# Sheet1.net
KiCad netlist of a schematic drawn in Altium Designer
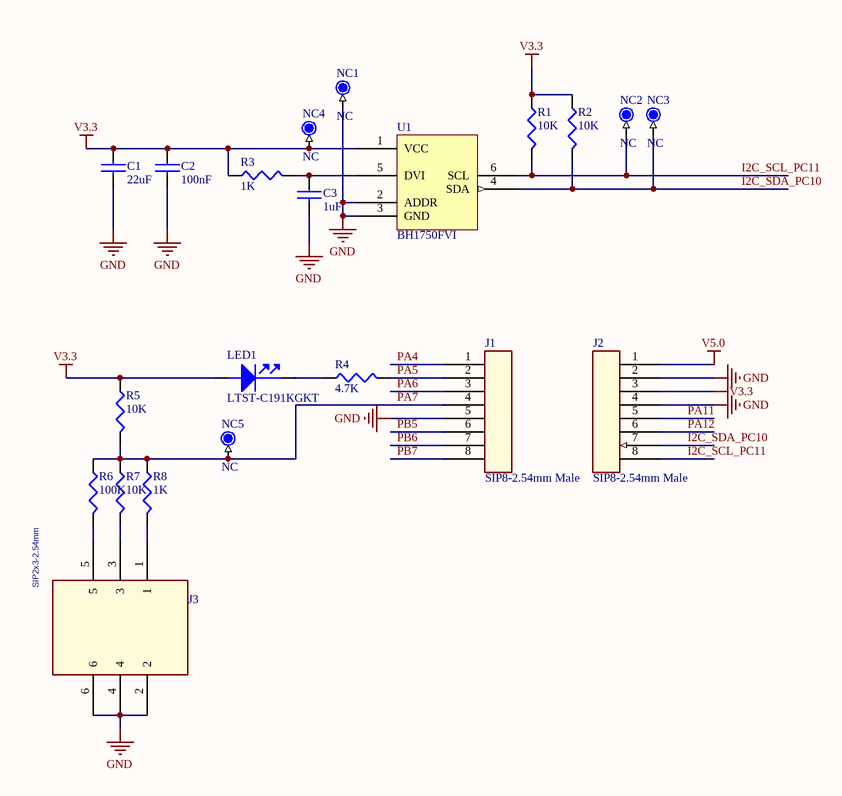
[diagram p0: Sheet1.SchDoc]

(export (version "E")
  (design (tool "Eeschema 10.0.6"))
  (components
    (comp (ref "C1") (value "22uF") (footprint "SC0805") (libsource (lib "EN-C200-OPT") (part "CAP NP")))
    (comp (ref "C2") (value "100nF") (footprint "SC0603") (libsource (lib "EN-C200-OPT") (part "CAP NP")))
    (comp (ref "C3") (value "1uF") (footprint "SC0603") (libsource (lib "EN-C200-OPT") (part "CAP NP")))
    (comp (ref "J1")
      (value "SIP8-2.54mm Male")
      (footprint "SIP-8P-100")
      (libsource (lib "EN-C200-OPT") (part "HEADER8"))
    )
    (comp (ref "J2")
      (value "SIP8-2.54mm Male")
      (footprint "SIP-8P-100")
      (libsource (lib "") (part "HEADER8_1"))
    )
    (comp (ref "J3")
      (value "SIP2x3-2.54mm")
      (footprint "SIP-2X3P-100")
      (libsource (lib "EN-C200-OPT") (part "CON2X3"))
    )
    (comp (ref "LED1")
      (value "LTST-C191KGKT")
      (footprint "HSD0603-LED")
      (libsource (lib "EN-C200-OPT") (part "LED"))
    )
    (comp (ref "NC1") (value "NC") (footprint "TP32-SMD") (libsource (lib "EN-C200-OPT") (part "TP")))
    (comp (ref "NC2") (value "NC") (footprint "TP32-SMD") (libsource (lib "EN-C200-OPT") (part "TP")))
    (comp (ref "NC3") (value "NC") (footprint "TP32-SMD") (libsource (lib "EN-C200-OPT") (part "TP")))
    (comp (ref "NC4") (value "NC") (footprint "TP32-SMD") (libsource (lib "EN-C200-OPT") (part "TP")))
    (comp (ref "NC5") (value "NC") (footprint "TP32-SMD") (libsource (lib "EN-C200-OPT") (part "TP")))
    (comp (ref "R1") (value "10K") (footprint "SR0603") (libsource (lib "EN-C200-OPT") (part "RESISTOR")))
    (comp (ref "R2") (value "10K") (footprint "SR0603") (libsource (lib "EN-C200-OPT") (part "RESISTOR")))
    (comp (ref "R3") (value "1K") (footprint "SR0603") (libsource (lib "EN-C200-OPT") (part "RESISTOR")))
    (comp (ref "R4") (value "4.7K") (footprint "SR0603") (libsource (lib "EN-C200-OPT") (part "RESISTOR")))
    (comp (ref "R5") (value "10K") (footprint "SR0603") (libsource (lib "EN-C200-OPT") (part "RESISTOR")))
    (comp (ref "R6") (value "100K") (footprint "SR0603") (libsource (lib "EN-C200-OPT") (part "RESISTOR")))
    (comp (ref "R7") (value "10K") (footprint "SR0603") (libsource (lib "EN-C200-OPT") (part "RESISTOR")))
    (comp (ref "R8") (value "1K") (footprint "SR0603") (libsource (lib "EN-C200-OPT") (part "RESISTOR")))
    (comp (ref "U1")
      (value "BH1750FVI")
      (footprint "sop6-20-105")
      (description "16 位数字输出型环境光强度传感器 ， I2C  BUS/-40 ℃ ～ +85 ℃")
      (libsource (lib "Schlib1") (part "BH1750FVI"))
    )
  )
  (nets
    (net (code "1") (name "/I2C_SCL_PC11") (class "Default")
      (node (ref "J2") (pin "8") (pinfunction "8_8") (pintype "passive"))
      (node (ref "NC2") (pin "1") (pinfunction "1_1") (pintype "input"))
      (node (ref "R1") (pin "2") (pinfunction "2_2") (pintype "passive"))
      (node (ref "U1") (pin "6") (pinfunction "SCL_6") (pintype "passive"))
    )
    (net (code "2") (name "/I2C_SDA_PC10") (class "Default")
      (node (ref "J2") (pin "7") (pinfunction "7_7") (pintype "input"))
      (node (ref "NC3") (pin "1") (pinfunction "1_1") (pintype "input"))
      (node (ref "R2") (pin "2") (pinfunction "2_2") (pintype "passive"))
      (node (ref "U1") (pin "4") (pinfunction "SDA_4") (pintype "output"))
    )
    (net (code "3") (name "/PA4") (class "Default")
      (node (ref "J1") (pin "1") (pinfunction "1_1") (pintype "passive"))
    )
    (net (code "4") (name "/PA5") (class "Default")
      (node (ref "J1") (pin "2") (pinfunction "2_2") (pintype "passive"))
      (node (ref "R4") (pin "2") (pinfunction "2_2") (pintype "passive"))
    )
    (net (code "5") (name "/PA6") (class "Default")
      (node (ref "J1") (pin "3") (pinfunction "3_3") (pintype "passive"))
    )
    (net (code "6") (name "/PA7") (class "Default")
      (node (ref "J1") (pin "4") (pinfunction "4_4") (pintype "passive"))
      (node (ref "NC5") (pin "1") (pinfunction "1_1") (pintype "input"))
      (node (ref "R5") (pin "2") (pinfunction "2_2") (pintype "passive"))
      (node (ref "R6") (pin "1") (pinfunction "1_1") (pintype "passive"))
      (node (ref "R7") (pin "1") (pinfunction "1_1") (pintype "passive"))
      (node (ref "R8") (pin "1") (pinfunction "1_1") (pintype "passive"))
    )
    (net (code "7") (name "/PA11") (class "Default")
      (node (ref "J2") (pin "5") (pinfunction "5_5") (pintype "passive"))
    )
    (net (code "8") (name "/PA12") (class "Default")
      (node (ref "J2") (pin "6") (pinfunction "6_6") (pintype "passive"))
    )
    (net (code "9") (name "/PB5") (class "Default")
      (node (ref "J1") (pin "6") (pinfunction "6_6") (pintype "passive"))
    )
    (net (code "10") (name "/PB6") (class "Default")
      (node (ref "J1") (pin "7") (pinfunction "7_7") (pintype "passive"))
    )
    (net (code "11") (name "/PB7") (class "Default")
      (node (ref "J1") (pin "8") (pinfunction "8_8") (pintype "passive"))
    )
    (net (code "12") (name "GND") (class "Default")
      (node (ref "C1") (pin "2") (pinfunction "2_2") (pintype "passive"))
      (node (ref "C2") (pin "2") (pinfunction "2_2") (pintype "passive"))
      (node (ref "C3") (pin "2") (pinfunction "2_2") (pintype "passive"))
      (node (ref "J1") (pin "5") (pinfunction "5_5") (pintype "passive"))
      (node (ref "J2") (pin "2") (pinfunction "2_2") (pintype "passive"))
      (node (ref "J2") (pin "4") (pinfunction "4_4") (pintype "passive"))
      (node (ref "J3") (pin "2") (pinfunction "2_2") (pintype "passive"))
      (node (ref "J3") (pin "4") (pinfunction "4_4") (pintype "passive"))
      (node (ref "J3") (pin "6") (pinfunction "6_6") (pintype "passive"))
      (node (ref "NC1") (pin "1") (pinfunction "1_1") (pintype "input"))
      (node (ref "U1") (pin "2") (pinfunction "ADDR_2") (pintype "passive"))
      (node (ref "U1") (pin "3") (pinfunction "GND_3") (pintype "passive"))
    )
    (net (code "13") (name "Net-(J3-Pad1)") (class "Default")
      (node (ref "J3") (pin "1") (pinfunction "1_1") (pintype "passive"))
      (node (ref "R8") (pin "2") (pinfunction "2_2") (pintype "passive"))
    )
    (net (code "14") (name "Net-(J3-Pad3)") (class "Default")
      (node (ref "J3") (pin "3") (pinfunction "3_3") (pintype "passive"))
      (node (ref "R7") (pin "2") (pinfunction "2_2") (pintype "passive"))
    )
    (net (code "15") (name "Net-(J3-Pad5)") (class "Default")
      (node (ref "J3") (pin "5") (pinfunction "5_5") (pintype "passive"))
      (node (ref "R6") (pin "2") (pinfunction "2_2") (pintype "passive"))
    )
    (net (code "16") (name "Net-(LED1-Pad2)") (class "Default")
      (node (ref "LED1") (pin "2") (pinfunction "2_2") (pintype "passive"))
      (node (ref "R4") (pin "1") (pinfunction "1_1") (pintype "passive"))
    )
    (net (code "17") (name "Net-(U1-DVI)") (class "Default")
      (node (ref "C3") (pin "1") (pinfunction "1_1") (pintype "passive"))
      (node (ref "R3") (pin "2") (pinfunction "2_2") (pintype "passive"))
      (node (ref "U1") (pin "5") (pinfunction "DVI_5") (pintype "passive"))
    )
    (net (code "18") (name "V3.3") (class "Default")
      (node (ref "C1") (pin "1") (pinfunction "1_1") (pintype "passive"))
      (node (ref "C2") (pin "1") (pinfunction "1_1") (pintype "passive"))
      (node (ref "J2") (pin "3") (pinfunction "3_3") (pintype "passive"))
      (node (ref "LED1") (pin "1") (pinfunction "1_1") (pintype "passive"))
      (node (ref "NC4") (pin "1") (pinfunction "1_1") (pintype "input"))
      (node (ref "R1") (pin "1") (pinfunction "1_1") (pintype "passive"))
      (node (ref "R2") (pin "1") (pinfunction "1_1") (pintype "passive"))
      (node (ref "R3") (pin "1") (pinfunction "1_1") (pintype "passive"))
      (node (ref "R5") (pin "1") (pinfunction "1_1") (pintype "passive"))
      (node (ref "U1") (pin "1") (pinfunction "VCC_1") (pintype "passive"))
    )
    (net (code "19") (name "V5.0") (class "Default")
      (node (ref "J2") (pin "1") (pinfunction "1_1") (pintype "passive"))
    )
  )
)
